# Etch_A_Sketch.net
KiCad netlist of a schematic drawn in EAGLE
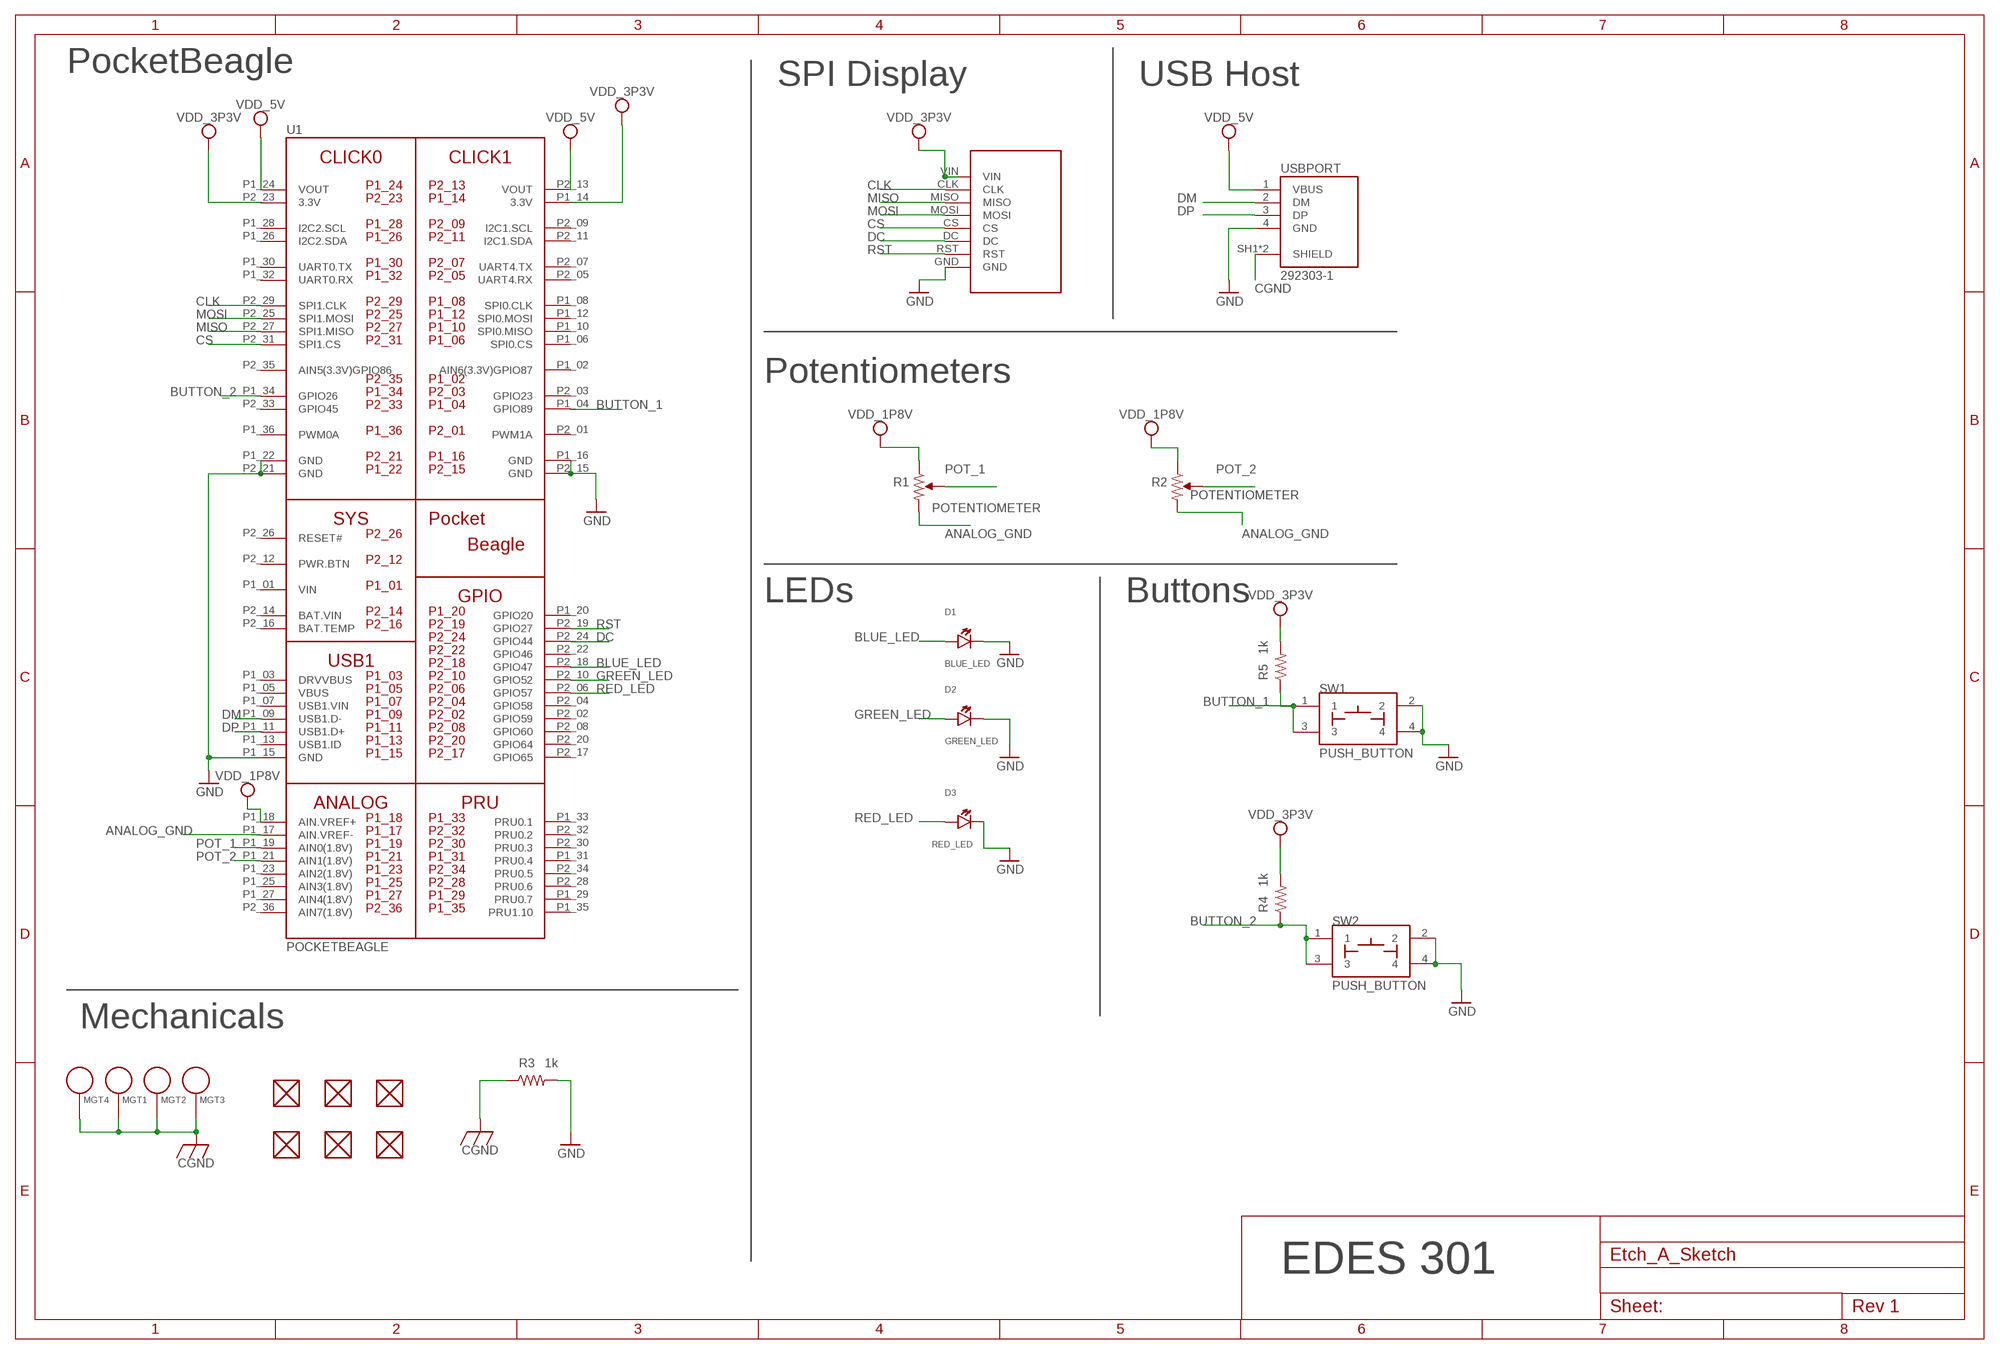
[diagram p0: schematic, sheet 1]

(export (version "E")
  (design (tool "Eeschema 10.0.6"))
  (components
    (comp (ref "D1")
      (value "BLUE_LED")
      (footprint "eagle-import:EIA-STD")
      (libsource (lib "eagle-import") (part "LED"))
    )
    (comp (ref "D2")
      (value "GREEN_LED")
      (footprint "eagle-import:EIA-STD")
      (libsource (lib "eagle-import") (part "LED"))
    )
    (comp (ref "D3")
      (value "RED_LED")
      (footprint "eagle-import:EIA-STD")
      (libsource (lib "eagle-import") (part "LED"))
    )
    (comp (ref "FUD1")
      (value "FIDUCIAL")
      (footprint "eagle-import:FIDUCIAL_40MIL")
      (libsource (lib "eagle-import") (part "FIDUCIAL"))
    )
    (comp (ref "FUD2")
      (value "FIDUCIAL")
      (footprint "eagle-import:FIDUCIAL_40MIL")
      (libsource (lib "eagle-import") (part "FIDUCIAL"))
    )
    (comp (ref "FUD3")
      (value "FIDUCIAL")
      (footprint "eagle-import:FIDUCIAL_40MIL")
      (libsource (lib "eagle-import") (part "FIDUCIAL"))
    )
    (comp (ref "FUD4")
      (value "FIDUCIAL")
      (footprint "eagle-import:FIDUCIAL_40MIL")
      (libsource (lib "eagle-import") (part "FIDUCIAL"))
    )
    (comp (ref "FUD5")
      (value "FIDUCIAL")
      (footprint "eagle-import:FIDUCIAL_40MIL")
      (libsource (lib "eagle-import") (part "FIDUCIAL"))
    )
    (comp (ref "FUD6")
      (value "FIDUCIAL")
      (footprint "eagle-import:FIDUCIAL_40MIL")
      (libsource (lib "eagle-import") (part "FIDUCIAL"))
    )
    (comp (ref "MGT1")
      (value "MOUNTING_HOLE")
      (footprint "eagle-import:MOUNTING_HOLE")
      (libsource (lib "eagle-import") (part "MOUNTING_HOLE"))
    )
    (comp (ref "MGT2")
      (value "MOUNTING_HOLE")
      (footprint "eagle-import:MOUNTING_HOLE")
      (libsource (lib "eagle-import") (part "MOUNTING_HOLE"))
    )
    (comp (ref "MGT3")
      (value "MOUNTING_HOLE")
      (footprint "eagle-import:MOUNTING_HOLE")
      (libsource (lib "eagle-import") (part "MOUNTING_HOLE"))
    )
    (comp (ref "MGT4")
      (value "MOUNTING_HOLE")
      (footprint "eagle-import:MOUNTING_HOLE")
      (libsource (lib "eagle-import") (part "MOUNTING_HOLE"))
    )
    (comp (ref "R1")
      (value "POTENTIOMETER")
      (footprint "eagle-import:POT-PO90S")
      (libsource (lib "eagle-import") (part "POTENTIOMETER"))
    )
    (comp (ref "R2")
      (value "POTENTIOMETER")
      (footprint "eagle-import:POT-PO90S")
      (libsource (lib "eagle-import") (part "POTENTIOMETER"))
    )
    (comp (ref "R3")
      (value "1k")
      (footprint "eagle-import:R0603")
      (libsource (lib "eagle-import") (part "R_R0603"))
    )
    (comp (ref "R4")
      (value "1k")
      (footprint "eagle-import:R0603")
      (libsource (lib "eagle-import") (part "R_R0603"))
    )
    (comp (ref "R5")
      (value "1k")
      (footprint "eagle-import:R0603")
      (libsource (lib "eagle-import") (part "R_R0603"))
    )
    (comp (ref "SPIDISPLAY")
      (value "SCREEN")
      (footprint "eagle-import:SCREEN")
      (libsource (lib "eagle-import") (part "SCREEN"))
    )
    (comp (ref "SW1")
      (value "PUSH_BUTTON")
      (footprint "eagle-import:BUTTON_12.5MM")
      (libsource (lib "eagle-import") (part "PUSH_BUTTON"))
    )
    (comp (ref "SW2")
      (value "PUSH_BUTTON")
      (footprint "eagle-import:BUTTON_12.5MM")
      (libsource (lib "eagle-import") (part "PUSH_BUTTON"))
    )
    (comp (ref "U1")
      (value "POCKETBEAGLE")
      (footprint "eagle-import:POCKETBEAGLE")
      (libsource (lib "eagle-import") (part "POCKETBEAGLE"))
    )
    (comp (ref "USBPORT")
      (value "292303-1")
      (footprint "eagle-import:TE_292303-1")
      (fields (field (name "MF") "TE Connectivity"))
      (libsource (lib "eagle-import") (part "292303-1"))
    )
  )
  (nets
    (net (code "1") (name "/ANALOG_GND") (class "Default")
      (node (ref "R1") (pin "CW") (pinfunction "CW_CW") (pintype "passive"))
      (node (ref "R2") (pin "CW") (pinfunction "CW_CW") (pintype "passive"))
      (node (ref "U1") (pin "P1_17") (pinfunction "AIN.VREF-_P1_17") (pintype "input"))
    )
    (net (code "2") (name "/BAT.VIN") (class "Default")
      (node (ref "U1") (pin "P2_14") (pinfunction "BAT.VIN_P2_14") (pintype "power_in"))
    )
    (net (code "3") (name "/BLUE_LED") (class "Default")
      (node (ref "D1") (pin "ANODE") (pinfunction "ANODE_ANODE") (pintype "bidirectional"))
      (node (ref "U1") (pin "P2_18") (pinfunction "GPIO47_P2_18") (pintype "bidirectional"))
    )
    (net (code "4") (name "/BUTTON_1") (class "Default")
      (node (ref "R5") (pin "1") (pinfunction "1_1") (pintype "passive"))
      (node (ref "SW1") (pin "1") (pinfunction "1_1") (pintype "bidirectional"))
      (node (ref "SW1") (pin "3") (pinfunction "3_3") (pintype "bidirectional"))
      (node (ref "U1") (pin "P1_04") (pinfunction "GPIO89_P1_04") (pintype "bidirectional"))
    )
    (net (code "5") (name "/BUTTON_2") (class "Default")
      (node (ref "R4") (pin "1") (pinfunction "1_1") (pintype "passive"))
      (node (ref "SW2") (pin "1") (pinfunction "1_1") (pintype "bidirectional"))
      (node (ref "SW2") (pin "3") (pinfunction "3_3") (pintype "bidirectional"))
      (node (ref "U1") (pin "P1_34") (pinfunction "GPIO26_P1_34") (pintype "bidirectional"))
    )
    (net (code "6") (name "/CLK") (class "Default")
      (node (ref "SPIDISPLAY") (pin "CLK") (pinfunction "CLK_CLK") (pintype "bidirectional"))
      (node (ref "U1") (pin "P2_29") (pinfunction "SPI1.CLK_P2_29") (pintype "bidirectional"))
    )
    (net (code "7") (name "/CS") (class "Default")
      (node (ref "SPIDISPLAY") (pin "CS") (pinfunction "CS_CS") (pintype "bidirectional"))
      (node (ref "U1") (pin "P2_31") (pinfunction "SPI1.CS_P2_31") (pintype "bidirectional"))
    )
    (net (code "8") (name "/DC") (class "Default")
      (node (ref "SPIDISPLAY") (pin "DC") (pinfunction "DC_DC") (pintype "bidirectional"))
      (node (ref "U1") (pin "P2_24") (pinfunction "GPIO44_P2_24") (pintype "bidirectional"))
    )
    (net (code "9") (name "/DM") (class "Default")
      (node (ref "U1") (pin "P1_09") (pinfunction "USB1.D-_P1_09") (pintype "bidirectional"))
      (node (ref "USBPORT") (pin "2") (pinfunction "DM_2") (pintype "passive"))
    )
    (net (code "10") (name "/DP") (class "Default")
      (node (ref "U1") (pin "P1_11") (pinfunction "USB1.D+_P1_11") (pintype "bidirectional"))
      (node (ref "USBPORT") (pin "3") (pinfunction "DP_3") (pintype "passive"))
    )
    (net (code "11") (name "/GREEN_LED") (class "Default")
      (node (ref "D2") (pin "ANODE") (pinfunction "ANODE_ANODE") (pintype "bidirectional"))
      (node (ref "U1") (pin "P2_10") (pinfunction "GPIO52_P2_10") (pintype "bidirectional"))
    )
    (net (code "12") (name "/MISO") (class "Default")
      (node (ref "SPIDISPLAY") (pin "MISO") (pinfunction "MISO_MISO") (pintype "bidirectional"))
      (node (ref "U1") (pin "P2_27") (pinfunction "SPI1.MISO_P2_27") (pintype "bidirectional"))
    )
    (net (code "13") (name "/MOSI") (class "Default")
      (node (ref "SPIDISPLAY") (pin "MOSI") (pinfunction "MOSI_MOSI") (pintype "bidirectional"))
      (node (ref "U1") (pin "P2_25") (pinfunction "SPI1.MOSI_P2_25") (pintype "bidirectional"))
    )
    (net (code "14") (name "/POT_1") (class "Default")
      (node (ref "R1") (pin "S") (pinfunction "S_S") (pintype "bidirectional"))
      (node (ref "U1") (pin "P1_19") (pinfunction "AIN0(1.8V)_P1_19") (pintype "input"))
    )
    (net (code "15") (name "/POT_2") (class "Default")
      (node (ref "R2") (pin "S") (pinfunction "S_S") (pintype "bidirectional"))
      (node (ref "U1") (pin "P1_21") (pinfunction "AIN1(1.8V)_P1_21") (pintype "input"))
    )
    (net (code "16") (name "/RED_LED") (class "Default")
      (node (ref "D3") (pin "ANODE") (pinfunction "ANODE_ANODE") (pintype "bidirectional"))
      (node (ref "U1") (pin "P2_06") (pinfunction "GPIO57_P2_06") (pintype "bidirectional"))
    )
    (net (code "17") (name "/RST") (class "Default")
      (node (ref "SPIDISPLAY") (pin "RST") (pinfunction "RST_RST") (pintype "bidirectional"))
      (node (ref "U1") (pin "P2_19") (pinfunction "GPIO27_P2_19") (pintype "bidirectional"))
    )
    (net (code "18") (name "/VIN") (class "Default")
      (node (ref "U1") (pin "P1_01") (pinfunction "VIN_P1_01") (pintype "power_in"))
    )
    (net (code "19") (name "CGND") (class "Default")
      (node (ref "MGT1") (pin "P$1") (pinfunction "P$1_P$1") (pintype "bidirectional"))
      (node (ref "MGT2") (pin "P$1") (pinfunction "P$1_P$1") (pintype "bidirectional"))
      (node (ref "MGT3") (pin "P$1") (pinfunction "P$1_P$1") (pintype "bidirectional"))
      (node (ref "MGT4") (pin "P$1") (pinfunction "P$1_P$1") (pintype "bidirectional"))
      (node (ref "R3") (pin "1") (pinfunction "1_1") (pintype "passive"))
      (node (ref "USBPORT") (pin "SH1") (pinfunction "SHIELD_SH1") (pintype "passive"))
      (node (ref "USBPORT") (pin "SH2") (pinfunction "SHIELD_SH2") (pintype "passive"))
    )
    (net (code "20") (name "GND") (class "Default")
      (node (ref "D1") (pin "CATHODE") (pinfunction "CATHODE_CATHODE") (pintype "bidirectional"))
      (node (ref "D2") (pin "CATHODE") (pinfunction "CATHODE_CATHODE") (pintype "bidirectional"))
      (node (ref "D3") (pin "CATHODE") (pinfunction "CATHODE_CATHODE") (pintype "bidirectional"))
      (node (ref "R3") (pin "2") (pinfunction "2_2") (pintype "passive"))
      (node (ref "SPIDISPLAY") (pin "GND") (pinfunction "GND_GND") (pintype "bidirectional"))
      (node (ref "SW1") (pin "2") (pinfunction "2_2") (pintype "bidirectional"))
      (node (ref "SW1") (pin "4") (pinfunction "4_4") (pintype "bidirectional"))
      (node (ref "SW2") (pin "2") (pinfunction "2_2") (pintype "bidirectional"))
      (node (ref "SW2") (pin "4") (pinfunction "4_4") (pintype "bidirectional"))
      (node (ref "U1") (pin "P1_15") (pinfunction "GND_P1_15") (pintype "bidirectional"))
      (node (ref "U1") (pin "P1_16") (pinfunction "GND_P1_16") (pintype "power_in"))
      (node (ref "U1") (pin "P1_22") (pinfunction "GND_P1_22") (pintype "power_in"))
      (node (ref "U1") (pin "P2_15") (pinfunction "GND_P2_15") (pintype "power_in"))
      (node (ref "U1") (pin "P2_21") (pinfunction "GND_P2_21") (pintype "power_in"))
      (node (ref "USBPORT") (pin "4") (pinfunction "GND_4") (pintype "passive"))
    )
    (net (code "21") (name "VDD_1P8V") (class "Default")
      (node (ref "R1") (pin "CCW") (pinfunction "CCW_CCW") (pintype "passive"))
      (node (ref "R2") (pin "CCW") (pinfunction "CCW_CCW") (pintype "passive"))
      (node (ref "U1") (pin "P1_18") (pinfunction "AIN.VREF+_P1_18") (pintype "input"))
    )
    (net (code "22") (name "VDD_3P3V") (class "Default")
      (node (ref "R4") (pin "2") (pinfunction "2_2") (pintype "passive"))
      (node (ref "R5") (pin "2") (pinfunction "2_2") (pintype "passive"))
      (node (ref "SPIDISPLAY") (pin "VIN") (pinfunction "VIN_VIN") (pintype "bidirectional"))
      (node (ref "U1") (pin "P1_14") (pinfunction "3.3V_P1_14") (pintype "power_in"))
      (node (ref "U1") (pin "P2_23") (pinfunction "3.3V_P2_23") (pintype "power_in"))
    )
    (net (code "23") (name "VDD_5V") (class "Default")
      (node (ref "U1") (pin "P1_24") (pinfunction "VOUT_P1_24") (pintype "power_in"))
      (node (ref "U1") (pin "P2_13") (pinfunction "VOUT_P2_13") (pintype "power_in"))
      (node (ref "USBPORT") (pin "1") (pinfunction "VBUS_1") (pintype "passive"))
    )
    (net (code "24") (name "unconnected-(FUD1-PadP$1)") (class "Default")
      (node (ref "FUD1") (pin "P$1") (pinfunction "P$1_P$1") (pintype "no_connect"))
    )
    (net (code "25") (name "unconnected-(FUD2-PadP$1)") (class "Default")
      (node (ref "FUD2") (pin "P$1") (pinfunction "P$1_P$1") (pintype "no_connect"))
    )
    (net (code "26") (name "unconnected-(FUD3-PadP$1)") (class "Default")
      (node (ref "FUD3") (pin "P$1") (pinfunction "P$1_P$1") (pintype "no_connect"))
    )
    (net (code "27") (name "unconnected-(FUD4-PadP$1)") (class "Default")
      (node (ref "FUD4") (pin "P$1") (pinfunction "P$1_P$1") (pintype "no_connect"))
    )
    (net (code "28") (name "unconnected-(FUD5-PadP$1)") (class "Default")
      (node (ref "FUD5") (pin "P$1") (pinfunction "P$1_P$1") (pintype "no_connect"))
    )
    (net (code "29") (name "unconnected-(FUD6-PadP$1)") (class "Default")
      (node (ref "FUD6") (pin "P$1") (pinfunction "P$1_P$1") (pintype "no_connect"))
    )
    (net (code "30") (name "unconnected-(U1-AIN2(1.8V)-PadP1_23)") (class "Default")
      (node (ref "U1") (pin "P1_23") (pinfunction "AIN2(1.8V)_P1_23") (pintype "input"))
    )
    (net (code "31") (name "unconnected-(U1-AIN3(1.8V)-PadP1_25)") (class "Default")
      (node (ref "U1") (pin "P1_25") (pinfunction "AIN3(1.8V)_P1_25") (pintype "input"))
    )
    (net (code "32") (name "unconnected-(U1-AIN4(1.8V)-PadP1_27)") (class "Default")
      (node (ref "U1") (pin "P1_27") (pinfunction "AIN4(1.8V)_P1_27") (pintype "input"))
    )
    (net (code "33") (name "unconnected-(U1-AIN5(3.3V)GPIO86-PadP2_35)") (class "Default")
      (node (ref "U1") (pin "P2_35") (pinfunction "AIN5(3.3V)GPIO86_P2_35") (pintype "bidirectional"))
    )
    (net (code "34") (name "unconnected-(U1-AIN6(3.3V)GPIO87-PadP1_02)") (class "Default")
      (node (ref "U1") (pin "P1_02") (pinfunction "AIN6(3.3V)GPIO87_P1_02") (pintype "bidirectional"))
    )
    (net (code "35") (name "unconnected-(U1-AIN7(1.8V)-PadP2_36)") (class "Default")
      (node (ref "U1") (pin "P2_36") (pinfunction "AIN7(1.8V)_P2_36") (pintype "input"))
    )
    (net (code "36") (name "unconnected-(U1-BAT.TEMP-PadP2_16)") (class "Default")
      (node (ref "U1") (pin "P2_16") (pinfunction "BAT.TEMP_P2_16") (pintype "input"))
    )
    (net (code "37") (name "unconnected-(U1-DRVVBUS-PadP1_03)") (class "Default")
      (node (ref "U1") (pin "P1_03") (pinfunction "DRVVBUS_P1_03") (pintype "bidirectional"))
    )
    (net (code "38") (name "unconnected-(U1-GPIO20-PadP1_20)") (class "Default")
      (node (ref "U1") (pin "P1_20") (pinfunction "GPIO20_P1_20") (pintype "bidirectional"))
    )
    (net (code "39") (name "unconnected-(U1-GPIO23-PadP2_03)") (class "Default")
      (node (ref "U1") (pin "P2_03") (pinfunction "GPIO23_P2_03") (pintype "bidirectional"))
    )
    (net (code "40") (name "unconnected-(U1-GPIO45-PadP2_33)") (class "Default")
      (node (ref "U1") (pin "P2_33") (pinfunction "GPIO45_P2_33") (pintype "bidirectional"))
    )
    (net (code "41") (name "unconnected-(U1-GPIO46-PadP2_22)") (class "Default")
      (node (ref "U1") (pin "P2_22") (pinfunction "GPIO46_P2_22") (pintype "bidirectional"))
    )
    (net (code "42") (name "unconnected-(U1-GPIO58-PadP2_04)") (class "Default")
      (node (ref "U1") (pin "P2_04") (pinfunction "GPIO58_P2_04") (pintype "bidirectional"))
    )
    (net (code "43") (name "unconnected-(U1-GPIO59-PadP2_02)") (class "Default")
      (node (ref "U1") (pin "P2_02") (pinfunction "GPIO59_P2_02") (pintype "bidirectional"))
    )
    (net (code "44") (name "unconnected-(U1-GPIO60-PadP2_08)") (class "Default")
      (node (ref "U1") (pin "P2_08") (pinfunction "GPIO60_P2_08") (pintype "bidirectional"))
    )
    (net (code "45") (name "unconnected-(U1-GPIO64-PadP2_20)") (class "Default")
      (node (ref "U1") (pin "P2_20") (pinfunction "GPIO64_P2_20") (pintype "bidirectional"))
    )
    (net (code "46") (name "unconnected-(U1-GPIO65-PadP2_17)") (class "Default")
      (node (ref "U1") (pin "P2_17") (pinfunction "GPIO65_P2_17") (pintype "bidirectional"))
    )
    (net (code "47") (name "unconnected-(U1-I2C1.SCL-PadP2_09)") (class "Default")
      (node (ref "U1") (pin "P2_09") (pinfunction "I2C1.SCL_P2_09") (pintype "bidirectional"))
    )
    (net (code "48") (name "unconnected-(U1-I2C1.SDA-PadP2_11)") (class "Default")
      (node (ref "U1") (pin "P2_11") (pinfunction "I2C1.SDA_P2_11") (pintype "bidirectional"))
    )
    (net (code "49") (name "unconnected-(U1-I2C2.SCL-PadP1_28)") (class "Default")
      (node (ref "U1") (pin "P1_28") (pinfunction "I2C2.SCL_P1_28") (pintype "bidirectional"))
    )
    (net (code "50") (name "unconnected-(U1-I2C2.SDA-PadP1_26)") (class "Default")
      (node (ref "U1") (pin "P1_26") (pinfunction "I2C2.SDA_P1_26") (pintype "bidirectional"))
    )
    (net (code "51") (name "unconnected-(U1-PRU0.1-PadP1_33)") (class "Default")
      (node (ref "U1") (pin "P1_33") (pinfunction "PRU0.1_P1_33") (pintype "bidirectional"))
    )
    (net (code "52") (name "unconnected-(U1-PRU0.2-PadP2_32)") (class "Default")
      (node (ref "U1") (pin "P2_32") (pinfunction "PRU0.2_P2_32") (pintype "bidirectional"))
    )
    (net (code "53") (name "unconnected-(U1-PRU0.3-PadP2_30)") (class "Default")
      (node (ref "U1") (pin "P2_30") (pinfunction "PRU0.3_P2_30") (pintype "bidirectional"))
    )
    (net (code "54") (name "unconnected-(U1-PRU0.4-PadP1_31)") (class "Default")
      (node (ref "U1") (pin "P1_31") (pinfunction "PRU0.4_P1_31") (pintype "bidirectional"))
    )
    (net (code "55") (name "unconnected-(U1-PRU0.5-PadP2_34)") (class "Default")
      (node (ref "U1") (pin "P2_34") (pinfunction "PRU0.5_P2_34") (pintype "bidirectional"))
    )
    (net (code "56") (name "unconnected-(U1-PRU0.6-PadP2_28)") (class "Default")
      (node (ref "U1") (pin "P2_28") (pinfunction "PRU0.6_P2_28") (pintype "bidirectional"))
    )
    (net (code "57") (name "unconnected-(U1-PRU0.7-PadP1_29)") (class "Default")
      (node (ref "U1") (pin "P1_29") (pinfunction "PRU0.7_P1_29") (pintype "bidirectional"))
    )
    (net (code "58") (name "unconnected-(U1-PRU1.10-PadP1_35)") (class "Default")
      (node (ref "U1") (pin "P1_35") (pinfunction "PRU1.10_P1_35") (pintype "bidirectional"))
    )
    (net (code "59") (name "unconnected-(U1-PWM0A-PadP1_36)") (class "Default")
      (node (ref "U1") (pin "P1_36") (pinfunction "PWM0A_P1_36") (pintype "bidirectional"))
    )
    (net (code "60") (name "unconnected-(U1-PWM1A-PadP2_01)") (class "Default")
      (node (ref "U1") (pin "P2_01") (pinfunction "PWM1A_P2_01") (pintype "bidirectional"))
    )
    (net (code "61") (name "unconnected-(U1-PWR.BTN-PadP2_12)") (class "Default")
      (node (ref "U1") (pin "P2_12") (pinfunction "PWR.BTN_P2_12") (pintype "input"))
    )
    (net (code "62") (name "unconnected-(U1-RESET#-PadP2_26)") (class "Default")
      (node (ref "U1") (pin "P2_26") (pinfunction "RESET#_P2_26") (pintype "input"))
    )
    (net (code "63") (name "unconnected-(U1-SPI0.CLK-PadP1_08)") (class "Default")
      (node (ref "U1") (pin "P1_08") (pinfunction "SPI0.CLK_P1_08") (pintype "bidirectional"))
    )
    (net (code "64") (name "unconnected-(U1-SPI0.CS-PadP1_06)") (class "Default")
      (node (ref "U1") (pin "P1_06") (pinfunction "SPI0.CS_P1_06") (pintype "bidirectional"))
    )
    (net (code "65") (name "unconnected-(U1-SPI0.MISO-PadP1_10)") (class "Default")
      (node (ref "U1") (pin "P1_10") (pinfunction "SPI0.MISO_P1_10") (pintype "bidirectional"))
    )
    (net (code "66") (name "unconnected-(U1-SPI0.MOSI-PadP1_12)") (class "Default")
      (node (ref "U1") (pin "P1_12") (pinfunction "SPI0.MOSI_P1_12") (pintype "bidirectional"))
    )
    (net (code "67") (name "unconnected-(U1-UART0.RX-PadP1_32)") (class "Default")
      (node (ref "U1") (pin "P1_32") (pinfunction "UART0.RX_P1_32") (pintype "bidirectional"))
    )
    (net (code "68") (name "unconnected-(U1-UART0.TX-PadP1_30)") (class "Default")
      (node (ref "U1") (pin "P1_30") (pinfunction "UART0.TX_P1_30") (pintype "bidirectional"))
    )
    (net (code "69") (name "unconnected-(U1-UART4.RX-PadP2_05)") (class "Default")
      (node (ref "U1") (pin "P2_05") (pinfunction "UART4.RX_P2_05") (pintype "bidirectional"))
    )
    (net (code "70") (name "unconnected-(U1-UART4.TX-PadP2_07)") (class "Default")
      (node (ref "U1") (pin "P2_07") (pinfunction "UART4.TX_P2_07") (pintype "bidirectional"))
    )
    (net (code "71") (name "unconnected-(U1-USB1.ID-PadP1_13)") (class "Default")
      (node (ref "U1") (pin "P1_13") (pinfunction "USB1.ID_P1_13") (pintype "bidirectional"))
    )
    (net (code "72") (name "unconnected-(U1-USB1.VIN-PadP1_07)") (class "Default")
      (node (ref "U1") (pin "P1_07") (pinfunction "USB1.VIN_P1_07") (pintype "bidirectional"))
    )
    (net (code "73") (name "unconnected-(U1-VBUS-PadP1_05)") (class "Default")
      (node (ref "U1") (pin "P1_05") (pinfunction "VBUS_P1_05") (pintype "bidirectional"))
    )
  )
)
